# sheet3_pd_controller.net
KiCad netlist of a schematic drawn in Altium Designer
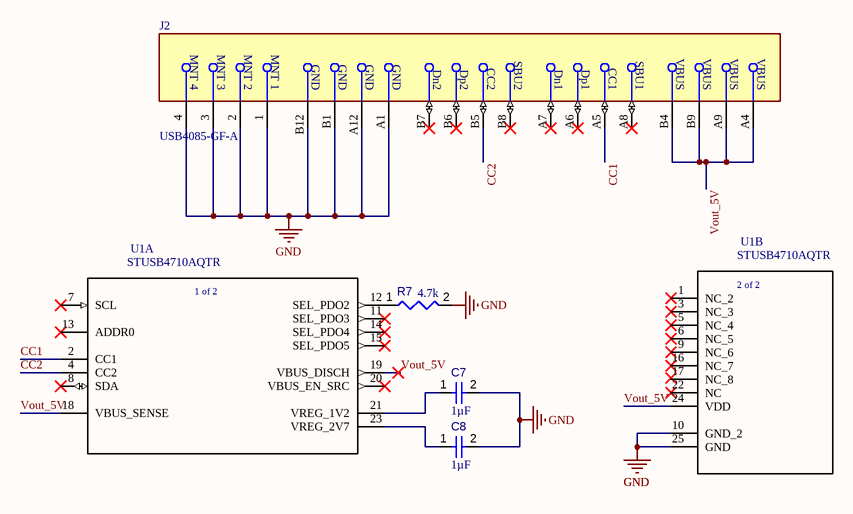
[diagram p0: sheet3_pd_controller.SchDoc]

(export (version "E")
  (design (tool "Eeschema 10.0.6"))
  (components
    (comp (ref "C7")
      (value "1µF")
      (footprint "CAPC2013X135X45NL10T25")
      (description "Chip Capacitor, 1 uF, +/- 10%, 50 V, 0805 (2012 Metric)")
      (fields (field (name "TOLERANCE") "10%") (field (name "Comment") "Capacitor 1 uF +/- 10% 50 V 0805"))
      (libsource (lib "University of Florida") (part "CAP-NP-2"))
    )
    (comp (ref "C8")
      (value "1µF")
      (footprint "CAPC2013X135X45NL10T25")
      (description "Chip Capacitor, 1 uF, +/- 10%, 50 V, 0805 (2012 Metric)")
      (fields (field (name "TOLERANCE") "10%") (field (name "Comment") "Capacitor 1 uF +/- 10% 50 V 0805"))
      (libsource (lib "University of Florida") (part "CAP-NP-2"))
    )
    (comp (ref "J2")
      (value "USB4085-GF-A")
      (footprint "FP-USB4085-GF-A-MFG")
      (description "CONN RCPT USB2.0 TYPE C 24POS RA")
      (libsource (lib "Altium Content Vault") (part "10fa745527c8b974685cbca3c197132"))
    )
    (comp (ref "R7")
      (value "4.7k")
      (footprint "RESC2013X70X40ML20T20")
      (description "Chip Resistor, 4.7 KOhm, +/- 1%, 0.125 W, -55 to 155 degC, 0805 (2012 Metric)")
      (fields (field (name "POWER") "125mW") (field (name "TOLERANCE") "1%"))
      (libsource (lib "University of Florida") (part "RES-2"))
    )
    (comp (ref "U1")
      (value "STUSB4710AQTR")
      (footprint "*QFN24EP_4X4_STM")
      (description "USB Controller USB 2.0 I2C Interface 24-QFN (4x4)")
      (fields (field (name "MF") "STMicroelectronics"))
      (libsource (lib "University of Florida") (part "STUSB4710AQTR"))
    )
  )
  (nets
    (net (code "1") (name "/CC1") (class "Default")
      (node (ref "J2") (pin "A5") (pinfunction "CC1_A5") (pintype "bidirectional"))
      (node (ref "U1") (pin "2") (pinfunction "CC1_2") (pintype "passive"))
    )
    (net (code "2") (name "/CC2") (class "Default")
      (node (ref "J2") (pin "B5") (pinfunction "CC2_B5") (pintype "bidirectional"))
      (node (ref "U1") (pin "4") (pinfunction "CC2_4") (pintype "passive"))
    )
    (net (code "3") (name "/Vout_5V") (class "Default")
      (node (ref "J2") (pin "A4") (pinfunction "VBUS_A4") (pintype "power_in"))
      (node (ref "J2") (pin "A9") (pinfunction "VBUS_A9") (pintype "power_in"))
      (node (ref "J2") (pin "B4") (pinfunction "VBUS_B4") (pintype "power_in"))
      (node (ref "J2") (pin "B9") (pinfunction "VBUS_B9") (pintype "power_in"))
      (node (ref "U1") (pin "18") (pinfunction "VBUS_SENSE_18") (pintype "passive"))
      (node (ref "U1") (pin "19") (pinfunction "VBUS_DISCH_19") (pintype "output"))
      (node (ref "U1") (pin "24") (pinfunction "VDD_24") (pintype "power_in"))
    )
    (net (code "4") (name "GND") (class "Default")
      (node (ref "C7") (pin "2") (pinfunction "2_2") (pintype "passive"))
      (node (ref "C8") (pin "2") (pinfunction "2_2") (pintype "passive"))
      (node (ref "J2") (pin "1") (pinfunction "MNT_1_1") (pintype "passive"))
      (node (ref "J2") (pin "2") (pinfunction "MNT_2_2") (pintype "passive"))
      (node (ref "J2") (pin "3") (pinfunction "MNT_3_3") (pintype "passive"))
      (node (ref "J2") (pin "4") (pinfunction "MNT_4_4") (pintype "passive"))
      (node (ref "J2") (pin "A1") (pinfunction "GND_A1") (pintype "power_in"))
      (node (ref "J2") (pin "A12") (pinfunction "GND_A12") (pintype "power_in"))
      (node (ref "J2") (pin "B1") (pinfunction "GND_B1") (pintype "power_in"))
      (node (ref "J2") (pin "B12") (pinfunction "GND_B12") (pintype "power_in"))
      (node (ref "R7") (pin "2") (pinfunction "2_2") (pintype "passive"))
      (node (ref "U1") (pin "10") (pinfunction "GND_2_10") (pintype "passive"))
      (node (ref "U1") (pin "25") (pinfunction "GND_25") (pintype "passive"))
    )
    (net (code "5") (name "Net-(U1A-SEL_PDO2)") (class "Default")
      (node (ref "R7") (pin "1") (pinfunction "1_1") (pintype "passive"))
      (node (ref "U1") (pin "12") (pinfunction "SEL_PDO2_12") (pintype "output"))
    )
    (net (code "6") (name "Net-(U1A-VREG_1V2)") (class "Default")
      (node (ref "C7") (pin "1") (pinfunction "1_1") (pintype "passive"))
      (node (ref "U1") (pin "21") (pinfunction "VREG_1V2_21") (pintype "passive"))
    )
    (net (code "7") (name "Net-(U1A-VREG_2V7)") (class "Default")
      (node (ref "C8") (pin "1") (pinfunction "1_1") (pintype "passive"))
      (node (ref "U1") (pin "23") (pinfunction "VREG_2V7_23") (pintype "passive"))
    )
    (net (code "8") (name "unconnected-(J2-Dn1-PadA7)") (class "Default")
      (node (ref "J2") (pin "A7") (pinfunction "Dn1_A7") (pintype "bidirectional+no_connect"))
    )
    (net (code "9") (name "unconnected-(J2-Dn2-PadB7)") (class "Default")
      (node (ref "J2") (pin "B7") (pinfunction "Dn2_B7") (pintype "bidirectional+no_connect"))
    )
    (net (code "10") (name "unconnected-(J2-Dp1-PadA6)") (class "Default")
      (node (ref "J2") (pin "A6") (pinfunction "Dp1_A6") (pintype "bidirectional+no_connect"))
    )
    (net (code "11") (name "unconnected-(J2-Dp2-PadB6)") (class "Default")
      (node (ref "J2") (pin "B6") (pinfunction "Dp2_B6") (pintype "bidirectional+no_connect"))
    )
    (net (code "12") (name "unconnected-(J2-SBU1-PadA8)") (class "Default")
      (node (ref "J2") (pin "A8") (pinfunction "SBU1_A8") (pintype "bidirectional+no_connect"))
    )
    (net (code "13") (name "unconnected-(J2-SBU2-PadB8)") (class "Default")
      (node (ref "J2") (pin "B8") (pinfunction "SBU2_B8") (pintype "bidirectional+no_connect"))
    )
    (net (code "14") (name "unconnected-(U1A-ADDR0-Pad13)") (class "Default")
      (node (ref "U1") (pin "13") (pinfunction "ADDR0_13") (pintype "passive+no_connect"))
    )
    (net (code "15") (name "unconnected-(U1A-SCL-Pad7)") (class "Default")
      (node (ref "U1") (pin "7") (pinfunction "SCL_7") (pintype "input+no_connect"))
    )
    (net (code "16") (name "unconnected-(U1A-SDA-Pad8)") (class "Default")
      (node (ref "U1") (pin "8") (pinfunction "SDA_8") (pintype "bidirectional+no_connect"))
    )
    (net (code "17") (name "unconnected-(U1A-SEL_PDO3-Pad11)") (class "Default")
      (node (ref "U1") (pin "11") (pinfunction "SEL_PDO3_11") (pintype "output+no_connect"))
    )
    (net (code "18") (name "unconnected-(U1A-SEL_PDO4-Pad14)") (class "Default")
      (node (ref "U1") (pin "14") (pinfunction "SEL_PDO4_14") (pintype "output+no_connect"))
    )
    (net (code "19") (name "unconnected-(U1A-SEL_PDO5-Pad15)") (class "Default")
      (node (ref "U1") (pin "15") (pinfunction "SEL_PDO5_15") (pintype "output+no_connect"))
    )
    (net (code "20") (name "unconnected-(U1A-VBUS_EN_SRC-Pad20)") (class "Default")
      (node (ref "U1") (pin "20") (pinfunction "VBUS_EN_SRC_20") (pintype "output+no_connect"))
    )
    (net (code "21") (name "unconnected-(U1B-NC-Pad22)") (class "Default")
      (node (ref "U1") (pin "22") (pinfunction "NC_22") (pintype "passive+no_connect"))
    )
    (net (code "22") (name "unconnected-(U1B-NC_2-Pad1)") (class "Default")
      (node (ref "U1") (pin "1") (pinfunction "NC_2_1") (pintype "passive+no_connect"))
    )
    (net (code "23") (name "unconnected-(U1B-NC_3-Pad3)") (class "Default")
      (node (ref "U1") (pin "3") (pinfunction "NC_3_3") (pintype "passive+no_connect"))
    )
    (net (code "24") (name "unconnected-(U1B-NC_4-Pad5)") (class "Default")
      (node (ref "U1") (pin "5") (pinfunction "NC_4_5") (pintype "passive+no_connect"))
    )
    (net (code "25") (name "unconnected-(U1B-NC_5-Pad6)") (class "Default")
      (node (ref "U1") (pin "6") (pinfunction "NC_5_6") (pintype "passive+no_connect"))
    )
    (net (code "26") (name "unconnected-(U1B-NC_6-Pad9)") (class "Default")
      (node (ref "U1") (pin "9") (pinfunction "NC_6_9") (pintype "passive+no_connect"))
    )
    (net (code "27") (name "unconnected-(U1B-NC_7-Pad16)") (class "Default")
      (node (ref "U1") (pin "16") (pinfunction "NC_7_16") (pintype "passive+no_connect"))
    )
    (net (code "28") (name "unconnected-(U1B-NC_8-Pad17)") (class "Default")
      (node (ref "U1") (pin "17") (pinfunction "NC_8_17") (pintype "passive"))
    )
  )
)
